# PowerSwitchBoard.net
KiCad netlist of a schematic drawn in Altium Designer
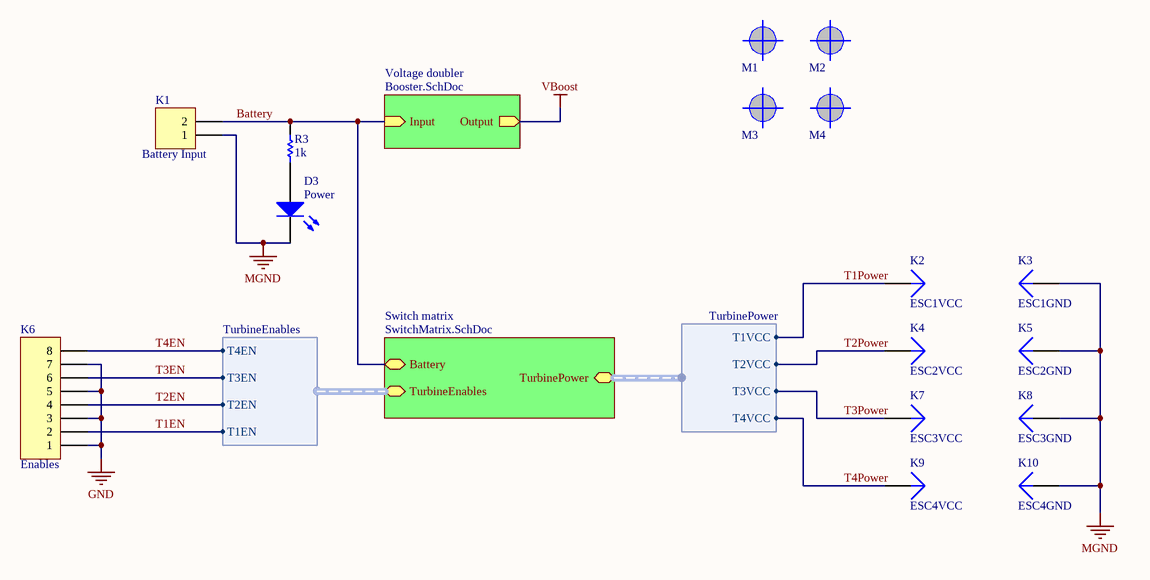
[diagram p0: PowerSwitchBoard.SchDoc]

(export (version "E")
  (design (tool "Eeschema 10.0.6"))
  (components
    (comp (ref "D3")
      (value "Power")
      (footprint "LED-3MM-GREEN")
      (description "Typical 3mm green LED")
      (fields (field (name "PUBLISHER") "Altium Limited"))
      (libsource (lib "Miscellaneous Devices") (part "LED0"))
    )
    (comp (ref "K1")
      (value "Battery Input")
      (footprint "CONN-SB-0.2-2WAY")
      (description "Header, 2-Pin")
      (fields (field (name "PUBLISHER") "Altium Limited"))
      (libsource (lib "Miscellaneous Connectors") (part "Header 2"))
    )
    (comp (ref "K2")
      (value "ESC1VCC")
      (footprint "CONN-BULLET-3.5-HF")
      (description "Plug")
      (fields (field (name "PUBLISHER") "Altium Limited"))
      (libsource (lib "Miscellaneous Connectors") (part "Plug"))
    )
    (comp (ref "K3")
      (value "ESC1GND")
      (footprint "CONN-BULLET-3.5-HF")
      (description "Plug")
      (fields (field (name "PUBLISHER") "Altium Limited"))
      (libsource (lib "Miscellaneous Connectors") (part "Plug"))
    )
    (comp (ref "K4")
      (value "ESC2VCC")
      (footprint "CONN-BULLET-3.5-HF")
      (description "Plug")
      (fields (field (name "PUBLISHER") "Altium Limited"))
      (libsource (lib "Miscellaneous Connectors") (part "Plug"))
    )
    (comp (ref "K5")
      (value "ESC2GND")
      (footprint "CONN-BULLET-3.5-HF")
      (description "Plug")
      (fields (field (name "PUBLISHER") "Altium Limited"))
      (libsource (lib "Miscellaneous Connectors") (part "Plug"))
    )
    (comp (ref "K6")
      (value "Enables")
      (footprint "CONN-HDR-0.1-1x8-SOCKH")
      (description "Header, 8-Pin, Right Angle")
      (fields (field (name "PUBLISHER") "Altium Limited"))
      (libsource (lib "Miscellaneous Connectors") (part "Header 8H"))
    )
    (comp (ref "K7")
      (value "ESC3VCC")
      (footprint "CONN-BULLET-3.5-HF")
      (description "Plug")
      (fields (field (name "PUBLISHER") "Altium Limited"))
      (libsource (lib "Miscellaneous Connectors") (part "Plug"))
    )
    (comp (ref "K8")
      (value "ESC3GND")
      (footprint "CONN-BULLET-3.5-HF")
      (description "Plug")
      (fields (field (name "PUBLISHER") "Altium Limited"))
      (libsource (lib "Miscellaneous Connectors") (part "Plug"))
    )
    (comp (ref "K9")
      (value "ESC4VCC")
      (footprint "CONN-BULLET-3.5-HF")
      (description "Plug")
      (fields (field (name "PUBLISHER") "Altium Limited"))
      (libsource (lib "Miscellaneous Connectors") (part "Plug"))
    )
    (comp (ref "K10")
      (value "ESC4GND")
      (footprint "CONN-BULLET-3.5-HF")
      (description "Plug")
      (fields (field (name "PUBLISHER") "Altium Limited"))
      (libsource (lib "Miscellaneous Connectors") (part "Plug"))
    )
    (comp (ref "M1")
      (value "Fiducial")
      (footprint "MECH-FID-ALL")
      (description "Fiducial marking")
      (libsource (lib "std") (part "Fiducial"))
    )
    (comp (ref "M2")
      (value "Fiducial")
      (footprint "MECH-FID-ALL")
      (description "Fiducial marking")
      (libsource (lib "std") (part "Fiducial"))
    )
    (comp (ref "M3")
      (value "Fiducial")
      (footprint "MECH-FID-ALL")
      (description "Fiducial marking")
      (libsource (lib "std") (part "Fiducial"))
    )
    (comp (ref "M4")
      (value "Fiducial")
      (footprint "MECH-FID-ALL")
      (description "Fiducial marking")
      (libsource (lib "std") (part "Fiducial"))
    )
    (comp (ref "R3")
      (value "1k")
      (footprint "RES-0.4")
      (description "Resistor")
      (fields (field (name "PUBLISHER") "Altium Limited"))
      (libsource (lib "Miscellaneous Devices") (part "Res1"))
    )
  )
  (nets
    (net (code "3") (name "/Battery") (class "Default")
      (node (ref "K1") (pin "2") (pinfunction "2_2") (pintype "passive"))
      (node (ref "R3") (pin "1") (pinfunction "1_1") (pintype "passive"))
    )
    (net (code "4") (name "/T1EN") (class "Default")
      (node (ref "K6") (pin "2") (pinfunction "2_2") (pintype "passive"))
    )
    (net (code "5") (name "/T1Power") (class "Default")
      (node (ref "K2") (pin "1") (pinfunction "1_1") (pintype "passive"))
    )
    (net (code "6") (name "/T2EN") (class "Default")
      (node (ref "K6") (pin "4") (pinfunction "4_4") (pintype "passive"))
    )
    (net (code "7") (name "/T2Power") (class "Default")
      (node (ref "K4") (pin "1") (pinfunction "1_1") (pintype "passive"))
    )
    (net (code "8") (name "/T3EN") (class "Default")
      (node (ref "K6") (pin "6") (pinfunction "6_6") (pintype "passive"))
    )
    (net (code "9") (name "/T3Power") (class "Default")
      (node (ref "K7") (pin "1") (pinfunction "1_1") (pintype "passive"))
    )
    (net (code "10") (name "/T4EN") (class "Default")
      (node (ref "K6") (pin "8") (pinfunction "8_8") (pintype "passive"))
    )
    (net (code "11") (name "/T4Power") (class "Default")
      (node (ref "K9") (pin "1") (pinfunction "1_1") (pintype "passive"))
    )
    (net (code "14") (name "GND") (class "Default")
      (node (ref "K6") (pin "1") (pinfunction "1_1") (pintype "passive"))
      (node (ref "K6") (pin "3") (pinfunction "3_3") (pintype "passive"))
      (node (ref "K6") (pin "5") (pinfunction "5_5") (pintype "passive"))
      (node (ref "K6") (pin "7") (pinfunction "7_7") (pintype "passive"))
    )
    (net (code "15") (name "MGND") (class "Default")
      (node (ref "D3") (pin "2") (pinfunction "K_2") (pintype "passive"))
      (node (ref "K1") (pin "1") (pinfunction "1_1") (pintype "passive"))
      (node (ref "K10") (pin "1") (pinfunction "1_1") (pintype "passive"))
      (node (ref "K3") (pin "1") (pinfunction "1_1") (pintype "passive"))
      (node (ref "K5") (pin "1") (pinfunction "1_1") (pintype "passive"))
      (node (ref "K8") (pin "1") (pinfunction "1_1") (pintype "passive"))
    )
    (net (code "16") (name "Net-(D3-A)") (class "Default")
      (node (ref "D3") (pin "1") (pinfunction "A_1") (pintype "passive"))
      (node (ref "R3") (pin "2") (pinfunction "2_2") (pintype "passive"))
    )
  )
)
